# StudioLab_SensorBoard.net
KiCad netlist of a schematic drawn in EAGLE
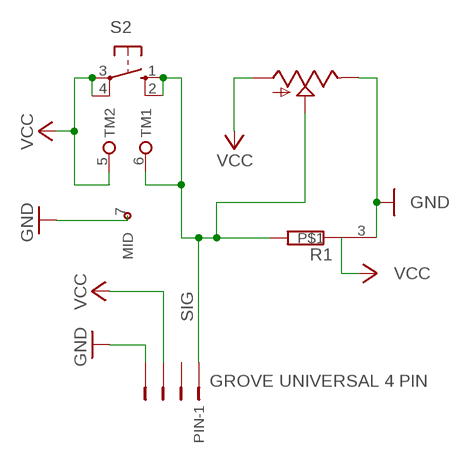
[diagram p0: schematic, sheet 1]

(export (version "E")
  (design (tool "Eeschema 10.0.6"))
  (components
    (comp (ref "PIN")
      (value "GROVE UNIVERSAL 4 PIN")
      (footprint "eagle-import:CON-JST_B4B-ZR")
      (fields (field (name "MF") "FARNELL") (field (name "MPN") "S4B-ZR(LF)(SN)"))
      (libsource (lib "eagle-import") (part "CON-JST_?4B-ZRB"))
    )
    (comp (ref "R1")
      (value "RES_PULL_UP_DOWNRES_PULL_UP_DOWN_ANGLE")
      (footprint "eagle-import:RES_PULL_UP_DOWN_ANGLE")
      (libsource (lib "eagle-import") (part "RES_PULL_UP_DOWNRES_PULL_UP_DOWN_ANGLE"))
    )
    (comp (ref "S2")
      (value "TERMINAL_TAC_SWITCH")
      (footprint "eagle-import:TERMINAL_TACTILE-PTH")
      (libsource (lib "eagle-import") (part "TERMINAL_TAC_SWITCH"))
    )
    (comp (ref "U$1")
      (value "SPARKFUN_POT")
      (footprint "eagle-import:SPARKFUN_ALPS_POT")
      (libsource (lib "eagle-import") (part "SPARKFUN_POT"))
    )
  )
  (nets
    (net (code "1") (name "/SIG") (class "Default")
      (node (ref "PIN") (pin "1") (pinfunction "1_1") (pintype "passive"))
      (node (ref "R1") (pin "1") (pinfunction "2_1") (pintype "passive"))
      (node (ref "S2") (pin "1") (pinfunction "3_1") (pintype "passive"))
      (node (ref "S2") (pin "2") (pinfunction "4_2") (pintype "passive"))
      (node (ref "S2") (pin "6") (pinfunction "TM1_6") (pintype "bidirectional"))
      (node (ref "U$1") (pin "P$2") (pinfunction "S_P$2") (pintype "passive"))
    )
    (net (code "2") (name "GND") (class "Default")
      (node (ref "PIN") (pin "4") (pinfunction "1_4") (pintype "passive"))
      (node (ref "R1") (pin "3") (pinfunction "P$1_3") (pintype "bidirectional"))
      (node (ref "S2") (pin "7") (pinfunction "MID_7") (pintype "bidirectional"))
      (node (ref "U$1") (pin "P$1") (pinfunction "E_P$1") (pintype "passive"))
    )
    (net (code "3") (name "VCC") (class "Default")
      (node (ref "PIN") (pin "3") (pinfunction "1_3") (pintype "passive"))
      (node (ref "R1") (pin "2") (pinfunction "1_2") (pintype "passive"))
      (node (ref "S2") (pin "3") (pinfunction "1_3") (pintype "passive"))
      (node (ref "S2") (pin "4") (pinfunction "2_4") (pintype "passive"))
      (node (ref "S2") (pin "5") (pinfunction "TM2_5") (pintype "bidirectional"))
      (node (ref "U$1") (pin "P$3") (pinfunction "A_P$3") (pintype "passive"))
    )
    (net (code "4") (name "unconnected-(PINB-1-Pad2)") (class "Default")
      (node (ref "PIN") (pin "2") (pinfunction "1_2") (pintype "passive"))
    )
  )
)
